# activity_monitor_v2.net
KiCad netlist of a schematic drawn in EAGLE
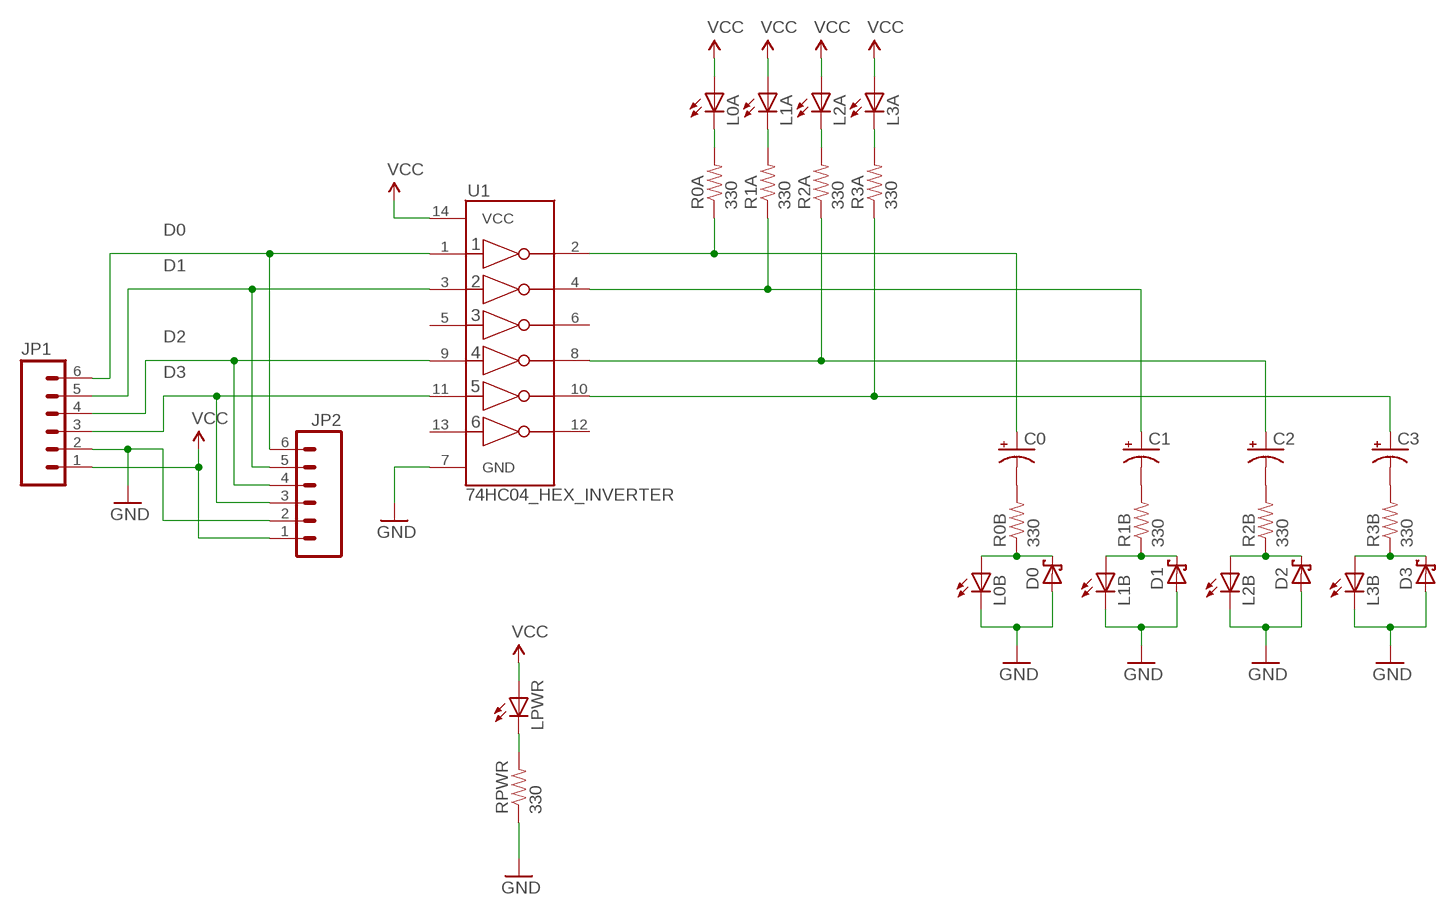
[diagram p0: schematic, sheet 1]

(export (version "E")
  (design (tool "Eeschema 10.0.6"))
  (components
    (comp (ref "C0")
      (value "CAP_POLPTH2")
      (footprint "eagle-import:CPOL-RADIAL-10UF-25V")
      (libsource (lib "eagle-import") (part "CAP_POLPTH2"))
    )
    (comp (ref "C1")
      (value "CAP_POLPTH2")
      (footprint "eagle-import:CPOL-RADIAL-10UF-25V")
      (libsource (lib "eagle-import") (part "CAP_POLPTH2"))
    )
    (comp (ref "C2")
      (value "CAP_POLPTH2")
      (footprint "eagle-import:CPOL-RADIAL-10UF-25V")
      (libsource (lib "eagle-import") (part "CAP_POLPTH2"))
    )
    (comp (ref "C3")
      (value "CAP_POLPTH2")
      (footprint "eagle-import:CPOL-RADIAL-10UF-25V")
      (libsource (lib "eagle-import") (part "CAP_POLPTH2"))
    )
    (comp (ref "D0")
      (value "SCHOTTKY-DIODEDO35-7")
      (footprint "eagle-import:DO35-7")
      (libsource (lib "eagle-import") (part "SCHOTTKY-DIODEDO35-7"))
    )
    (comp (ref "D1")
      (value "SCHOTTKY-DIODEDO35-7")
      (footprint "eagle-import:DO35-7")
      (libsource (lib "eagle-import") (part "SCHOTTKY-DIODEDO35-7"))
    )
    (comp (ref "D2")
      (value "SCHOTTKY-DIODEDO35-7")
      (footprint "eagle-import:DO35-7")
      (libsource (lib "eagle-import") (part "SCHOTTKY-DIODEDO35-7"))
    )
    (comp (ref "D3")
      (value "SCHOTTKY-DIODEDO35-7")
      (footprint "eagle-import:DO35-7")
      (libsource (lib "eagle-import") (part "SCHOTTKY-DIODEDO35-7"))
    )
    (comp (ref "JP1")
      (value "M06SIP")
      (footprint "eagle-import:1X06")
      (libsource (lib "eagle-import") (part "M06SIP"))
    )
    (comp (ref "JP2")
      (value "M06SIP")
      (footprint "eagle-import:1X06")
      (libsource (lib "eagle-import") (part "M06SIP"))
    )
    (comp (ref "L0A")
      (value "LED3MM")
      (footprint "eagle-import:LED3MM")
      (libsource (lib "eagle-import") (part "LED3MM"))
    )
    (comp (ref "L0B")
      (value "LED3MM")
      (footprint "eagle-import:LED3MM")
      (libsource (lib "eagle-import") (part "LED3MM"))
    )
    (comp (ref "L1A")
      (value "LED3MM")
      (footprint "eagle-import:LED3MM")
      (libsource (lib "eagle-import") (part "LED3MM"))
    )
    (comp (ref "L1B")
      (value "LED3MM")
      (footprint "eagle-import:LED3MM")
      (libsource (lib "eagle-import") (part "LED3MM"))
    )
    (comp (ref "L2A")
      (value "LED3MM")
      (footprint "eagle-import:LED3MM")
      (libsource (lib "eagle-import") (part "LED3MM"))
    )
    (comp (ref "L2B")
      (value "LED3MM")
      (footprint "eagle-import:LED3MM")
      (libsource (lib "eagle-import") (part "LED3MM"))
    )
    (comp (ref "L3A")
      (value "LED3MM")
      (footprint "eagle-import:LED3MM")
      (libsource (lib "eagle-import") (part "LED3MM"))
    )
    (comp (ref "L3B")
      (value "LED3MM")
      (footprint "eagle-import:LED3MM")
      (libsource (lib "eagle-import") (part "LED3MM"))
    )
    (comp (ref "LPWR")
      (value "LED3MM")
      (footprint "eagle-import:LED3MM")
      (libsource (lib "eagle-import") (part "LED3MM"))
    )
    (comp (ref "R0A")
      (value "330")
      (footprint "eagle-import:AXIAL-0.4")
      (libsource (lib "eagle-import") (part "RESISTORPTH-1/4W"))
    )
    (comp (ref "R0B")
      (value "330")
      (footprint "eagle-import:AXIAL-0.4")
      (libsource (lib "eagle-import") (part "RESISTORPTH-1/4W"))
    )
    (comp (ref "R1A")
      (value "330")
      (footprint "eagle-import:AXIAL-0.4")
      (libsource (lib "eagle-import") (part "RESISTORPTH-1/4W"))
    )
    (comp (ref "R1B")
      (value "330")
      (footprint "eagle-import:AXIAL-0.4")
      (libsource (lib "eagle-import") (part "RESISTORPTH-1/4W"))
    )
    (comp (ref "R2A")
      (value "330")
      (footprint "eagle-import:AXIAL-0.4")
      (libsource (lib "eagle-import") (part "RESISTORPTH-1/4W"))
    )
    (comp (ref "R2B")
      (value "330")
      (footprint "eagle-import:AXIAL-0.4")
      (libsource (lib "eagle-import") (part "RESISTORPTH-1/4W"))
    )
    (comp (ref "R3A")
      (value "330")
      (footprint "eagle-import:AXIAL-0.4")
      (libsource (lib "eagle-import") (part "RESISTORPTH-1/4W"))
    )
    (comp (ref "R3B")
      (value "330")
      (footprint "eagle-import:AXIAL-0.4")
      (libsource (lib "eagle-import") (part "RESISTORPTH-1/4W"))
    )
    (comp (ref "RPWR")
      (value "330")
      (footprint "eagle-import:AXIAL-0.4")
      (libsource (lib "eagle-import") (part "RESISTORPTH-1/4W"))
    )
    (comp (ref "U1")
      (value "74HC04_HEX_INVERTER")
      (footprint "eagle-import:DIL14")
      (libsource (lib "eagle-import") (part "74HC04_HEX_INVERTER"))
    )
  )
  (nets
    (net (code "1") (name "/D0") (class "Default")
      (node (ref "JP1") (pin "6") (pinfunction "6_6") (pintype "passive"))
      (node (ref "JP2") (pin "6") (pinfunction "6_6") (pintype "passive"))
      (node (ref "U1") (pin "1") (pinfunction "1A_1") (pintype "input"))
    )
    (net (code "2") (name "/D1") (class "Default")
      (node (ref "JP1") (pin "5") (pinfunction "5_5") (pintype "passive"))
      (node (ref "JP2") (pin "5") (pinfunction "5_5") (pintype "passive"))
      (node (ref "U1") (pin "3") (pinfunction "2A_3") (pintype "input"))
    )
    (net (code "3") (name "/D2") (class "Default")
      (node (ref "JP1") (pin "4") (pinfunction "4_4") (pintype "passive"))
      (node (ref "JP2") (pin "4") (pinfunction "4_4") (pintype "passive"))
      (node (ref "U1") (pin "9") (pinfunction "4A_9") (pintype "input"))
    )
    (net (code "4") (name "/D3") (class "Default")
      (node (ref "JP1") (pin "3") (pinfunction "3_3") (pintype "passive"))
      (node (ref "JP2") (pin "3") (pinfunction "3_3") (pintype "passive"))
      (node (ref "U1") (pin "11") (pinfunction "5A_11") (pintype "input"))
    )
    (net (code "5") (name "GND") (class "Default")
      (node (ref "D0") (pin "A") (pinfunction "A_A") (pintype "passive"))
      (node (ref "D1") (pin "A") (pinfunction "A_A") (pintype "passive"))
      (node (ref "D2") (pin "A") (pinfunction "A_A") (pintype "passive"))
      (node (ref "D3") (pin "A") (pinfunction "A_A") (pintype "passive"))
      (node (ref "JP1") (pin "2") (pinfunction "2_2") (pintype "passive"))
      (node (ref "JP2") (pin "2") (pinfunction "2_2") (pintype "passive"))
      (node (ref "L0B") (pin "K") (pinfunction "C_K") (pintype "passive"))
      (node (ref "L1B") (pin "K") (pinfunction "C_K") (pintype "passive"))
      (node (ref "L2B") (pin "K") (pinfunction "C_K") (pintype "passive"))
      (node (ref "L3B") (pin "K") (pinfunction "C_K") (pintype "passive"))
      (node (ref "RPWR") (pin "P$1") (pinfunction "1_P$1") (pintype "passive"))
      (node (ref "U1") (pin "7") (pinfunction "GND_7") (pintype "power_in"))
    )
    (net (code "6") (name "Net-(C0-+)") (class "Default")
      (node (ref "C0") (pin "1") (pinfunction "+_1") (pintype "passive"))
      (node (ref "R0A") (pin "P$1") (pinfunction "1_P$1") (pintype "passive"))
      (node (ref "U1") (pin "2") (pinfunction "1Y_2") (pintype "output"))
    )
    (net (code "7") (name "Net-(C0--)") (class "Default")
      (node (ref "C0") (pin "2") (pinfunction "-_2") (pintype "passive"))
      (node (ref "R0B") (pin "P$2") (pinfunction "2_P$2") (pintype "passive"))
    )
    (net (code "8") (name "Net-(C1-+)") (class "Default")
      (node (ref "C1") (pin "1") (pinfunction "+_1") (pintype "passive"))
      (node (ref "R1A") (pin "P$1") (pinfunction "1_P$1") (pintype "passive"))
      (node (ref "U1") (pin "4") (pinfunction "2Y_4") (pintype "output"))
    )
    (net (code "9") (name "Net-(C1--)") (class "Default")
      (node (ref "C1") (pin "2") (pinfunction "-_2") (pintype "passive"))
      (node (ref "R1B") (pin "P$2") (pinfunction "2_P$2") (pintype "passive"))
    )
    (net (code "10") (name "Net-(C2-+)") (class "Default")
      (node (ref "C2") (pin "1") (pinfunction "+_1") (pintype "passive"))
      (node (ref "R2A") (pin "P$1") (pinfunction "1_P$1") (pintype "passive"))
      (node (ref "U1") (pin "8") (pinfunction "4Y_8") (pintype "output"))
    )
    (net (code "11") (name "Net-(C2--)") (class "Default")
      (node (ref "C2") (pin "2") (pinfunction "-_2") (pintype "passive"))
      (node (ref "R2B") (pin "P$2") (pinfunction "2_P$2") (pintype "passive"))
    )
    (net (code "12") (name "Net-(C3-+)") (class "Default")
      (node (ref "C3") (pin "1") (pinfunction "+_1") (pintype "passive"))
      (node (ref "R3A") (pin "P$1") (pinfunction "1_P$1") (pintype "passive"))
      (node (ref "U1") (pin "10") (pinfunction "5Y_10") (pintype "output"))
    )
    (net (code "13") (name "Net-(C3--)") (class "Default")
      (node (ref "C3") (pin "2") (pinfunction "-_2") (pintype "passive"))
      (node (ref "R3B") (pin "P$2") (pinfunction "2_P$2") (pintype "passive"))
    )
    (net (code "14") (name "Net-(L0A-C)") (class "Default")
      (node (ref "L0A") (pin "K") (pinfunction "C_K") (pintype "passive"))
      (node (ref "R0A") (pin "P$2") (pinfunction "2_P$2") (pintype "passive"))
    )
    (net (code "15") (name "Net-(L1A-C)") (class "Default")
      (node (ref "L1A") (pin "K") (pinfunction "C_K") (pintype "passive"))
      (node (ref "R1A") (pin "P$2") (pinfunction "2_P$2") (pintype "passive"))
    )
    (net (code "16") (name "Net-(L2A-C)") (class "Default")
      (node (ref "L2A") (pin "K") (pinfunction "C_K") (pintype "passive"))
      (node (ref "R2A") (pin "P$2") (pinfunction "2_P$2") (pintype "passive"))
    )
    (net (code "17") (name "Net-(L3A-C)") (class "Default")
      (node (ref "L3A") (pin "K") (pinfunction "C_K") (pintype "passive"))
      (node (ref "R3A") (pin "P$2") (pinfunction "2_P$2") (pintype "passive"))
    )
    (net (code "18") (name "Net-(LPWR-C)") (class "Default")
      (node (ref "LPWR") (pin "K") (pinfunction "C_K") (pintype "passive"))
      (node (ref "RPWR") (pin "P$2") (pinfunction "2_P$2") (pintype "passive"))
    )
    (net (code "19") (name "Net-(R0B-1)") (class "Default")
      (node (ref "D0") (pin "C") (pinfunction "C_C") (pintype "passive"))
      (node (ref "L0B") (pin "A") (pinfunction "A_A") (pintype "passive"))
      (node (ref "R0B") (pin "P$1") (pinfunction "1_P$1") (pintype "passive"))
    )
    (net (code "20") (name "Net-(R1B-1)") (class "Default")
      (node (ref "D1") (pin "C") (pinfunction "C_C") (pintype "passive"))
      (node (ref "L1B") (pin "A") (pinfunction "A_A") (pintype "passive"))
      (node (ref "R1B") (pin "P$1") (pinfunction "1_P$1") (pintype "passive"))
    )
    (net (code "21") (name "Net-(R2B-1)") (class "Default")
      (node (ref "D2") (pin "C") (pinfunction "C_C") (pintype "passive"))
      (node (ref "L2B") (pin "A") (pinfunction "A_A") (pintype "passive"))
      (node (ref "R2B") (pin "P$1") (pinfunction "1_P$1") (pintype "passive"))
    )
    (net (code "22") (name "Net-(R3B-1)") (class "Default")
      (node (ref "D3") (pin "C") (pinfunction "C_C") (pintype "passive"))
      (node (ref "L3B") (pin "A") (pinfunction "A_A") (pintype "passive"))
      (node (ref "R3B") (pin "P$1") (pinfunction "1_P$1") (pintype "passive"))
    )
    (net (code "23") (name "VCC") (class "Default")
      (node (ref "JP1") (pin "1") (pinfunction "1_1") (pintype "passive"))
      (node (ref "JP2") (pin "1") (pinfunction "1_1") (pintype "passive"))
      (node (ref "L0A") (pin "A") (pinfunction "A_A") (pintype "passive"))
      (node (ref "L1A") (pin "A") (pinfunction "A_A") (pintype "passive"))
      (node (ref "L2A") (pin "A") (pinfunction "A_A") (pintype "passive"))
      (node (ref "L3A") (pin "A") (pinfunction "A_A") (pintype "passive"))
      (node (ref "LPWR") (pin "A") (pinfunction "A_A") (pintype "passive"))
      (node (ref "U1") (pin "14") (pinfunction "VCC_14") (pintype "power_in"))
    )
    (net (code "24") (name "unconnected-(U1-3A-Pad5)") (class "Default")
      (node (ref "U1") (pin "5") (pinfunction "3A_5") (pintype "input"))
    )
    (net (code "25") (name "unconnected-(U1-3Y-Pad6)") (class "Default")
      (node (ref "U1") (pin "6") (pinfunction "3Y_6") (pintype "output"))
    )
    (net (code "26") (name "unconnected-(U1-6A-Pad13)") (class "Default")
      (node (ref "U1") (pin "13") (pinfunction "6A_13") (pintype "input"))
    )
    (net (code "27") (name "unconnected-(U1-6Y-Pad12)") (class "Default")
      (node (ref "U1") (pin "12") (pinfunction "6Y_12") (pintype "output"))
    )
  )
)
